# power.net
KiCad netlist of a schematic drawn in Altium Designer
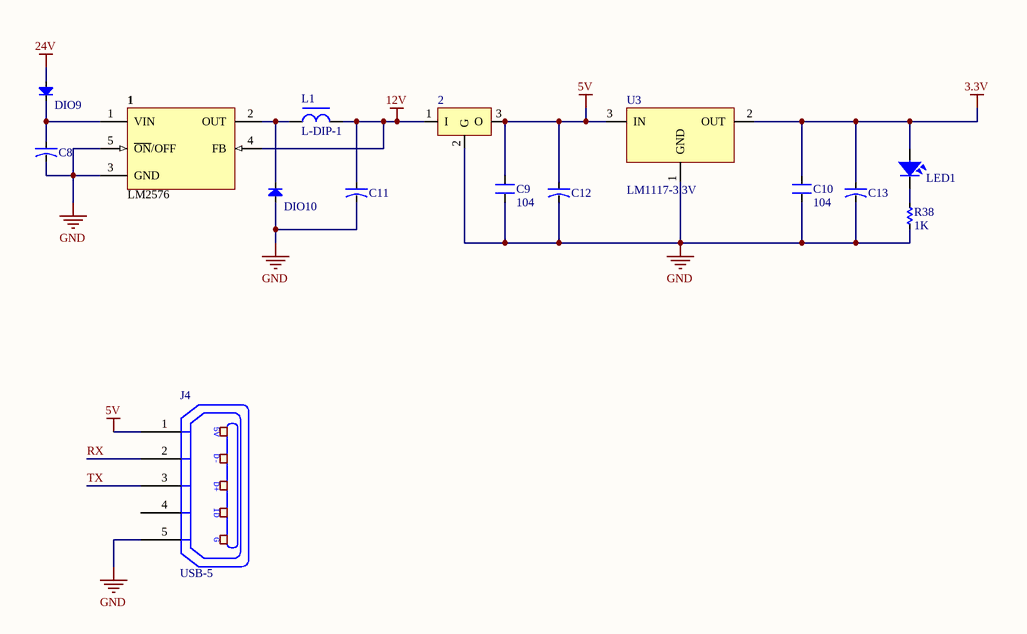
[diagram p0: power.SchDoc]

(export (version "E")
  (design (tool "Eeschema 10.0.6"))
  (components
    (comp (ref "1") (value "LM2576") (footprint "TO263") (libsource (lib "LIBRARY") (part "LM2576")))
    (comp (ref "2")
      (value "LM78xx")
      (footprint "TO252-123")
      (description "Positive Voltage Regulator")
      (fields (field (name "PUBLISHER") "Altium Limited"))
      (libsource (lib "LIBRARY") (part "LM78xx"))
    )
    (comp (ref "C8")
      (value "CN-ALU-SMD")
      (footprint "CAP-ALU-SMD-4.5x5x1.4")
      (description "Polarized Capacitor (Axial)")
      (fields (field (name "PUBLISHER") "Altium Limited"))
      (libsource (lib "LIBTanCN") (part "CN-ALU-SMD"))
    )
    (comp (ref "C9")
      (value "104")
      (footprint "SM-CAP-0805")
      (fields (field (name "DESIGNED BY") "VanDungEvn"))
      (libsource (lib "electronicvn-library1") (part "CN"))
    )
    (comp (ref "C10")
      (value "104")
      (footprint "SM-CAP-0805")
      (fields (field (name "DESIGNED BY") "VanDungEvn"))
      (libsource (lib "electronicvn-library1") (part "CN"))
    )
    (comp (ref "C11")
      (value "CN-ALU-SMD")
      (footprint "CAP-ALU-SMD-4.5x5x1.4")
      (description "Polarized Capacitor (Axial)")
      (fields (field (name "PUBLISHER") "Altium Limited"))
      (libsource (lib "LIBTanCN") (part "CN-ALU-SMD"))
    )
    (comp (ref "C12")
      (value "CN-ALU-SMD")
      (footprint "CAP-ALU-SMD-4.5x5x1.4")
      (description "Polarized Capacitor (Axial)")
      (fields (field (name "PUBLISHER") "Altium Limited"))
      (libsource (lib "LIBTanCN") (part "CN-ALU-SMD"))
    )
    (comp (ref "C13")
      (value "CN-ALU-SMD")
      (footprint "CAP-ALU-SMD-4.5x5x1.4")
      (description "Polarized Capacitor (Axial)")
      (fields (field (name "PUBLISHER") "Altium Limited"))
      (libsource (lib "LIBTanCN") (part "CN-ALU-SMD"))
    )
    (comp (ref "DIO9")
      (value "Diode SMD")
      (footprint "DIO-SMD-106")
      (description "Default Diode")
      (fields (field (name "PUBLISHER") "Altium Limited"))
      (libsource (lib "LIBRARY") (part "Diode SMD"))
    )
    (comp (ref "DIO10")
      (value "Diode SMD")
      (footprint "DIO-SMD-106")
      (description "Default Diode")
      (fields (field (name "PUBLISHER") "Altium Limited"))
      (libsource (lib "LIBRARY") (part "Diode SMD"))
    )
    (comp (ref "J4")
      (value "USB-5")
      (footprint "USB-M4")
      (fields
        (field (name "MANUFACTURER") "FCI")
        (field (name "MANUFACTURER PART NUMBER") "10118193-0001LF")
        (field (name ".CREATOR") "MM")
        (field (name ".CHECKED PCB") "RF")
        (field (name ".CHECKED SCH") "MM")
      )
      (libsource (lib "LIBRARY") (part "USB-5"))
    )
    (comp (ref "L1")
      (value "L-DIP-1")
      (footprint "L-DIP-M-13.5x6")
      (description "Inductor")
      (libsource (lib "LIBRARY") (part "L-DIP-1"))
    )
    (comp (ref "LED1") (value "LED") (footprint "LED-0805-Blue") (libsource (lib "LIBRARY") (part "LED SMD")))
    (comp (ref "R38")
      (value "1K")
      (footprint "RES-SMD-0805")
      (description "Resistor")
      (fields
        (field (name "MANUFACTURER") "Generic Components")
        (field (name "PUBLISHER") "Altium Hobart Technology Centre")
      )
      (libsource (lib "LIBRARY") (part "Res-SMD"))
    )
    (comp (ref "U3")
      (value "LM1117-3.3V")
      (footprint "SOT223")
      (description "800mA Low-Dropout Linear Regulator")
      (fields (field (name "CREATOR") "Nguyen Ba Bien"))
      (libsource (lib "LIBRARY") (part "LM1117"))
    )
  )
  (nets
    (net (code "1") (name "/RX") (class "Default")
      (node (ref "J4") (pin "2") (pinfunction "P2_2") (pintype "passive"))
    )
    (net (code "2") (name "/TX") (class "Default")
      (node (ref "J4") (pin "3") (pinfunction "P3_3") (pintype "passive"))
    )
    (net (code "3") (name "3.3V") (class "Default")
      (node (ref "C10") (pin "2") (pinfunction "2_2") (pintype "passive"))
      (node (ref "C13") (pin "1") (pinfunction "1_1") (pintype "passive"))
      (node (ref "LED1") (pin "1") (pinfunction "1_1") (pintype "passive"))
      (node (ref "U3") (pin "2") (pinfunction "OUT_2") (pintype "passive"))
    )
    (net (code "4") (name "5V") (class "Default")
      (node (ref "2") (pin "3") (pinfunction "O_3") (pintype "power_in"))
      (node (ref "C12") (pin "1") (pinfunction "1_1") (pintype "passive"))
      (node (ref "C9") (pin "2") (pinfunction "2_2") (pintype "passive"))
      (node (ref "J4") (pin "1") (pinfunction "P1_1") (pintype "passive"))
      (node (ref "U3") (pin "3") (pinfunction "IN_3") (pintype "passive"))
    )
    (net (code "5") (name "12V") (class "Default")
      (node (ref "1") (pin "4") (pinfunction "FB_4") (pintype "input"))
      (node (ref "2") (pin "1") (pinfunction "I_1") (pintype "power_in"))
      (node (ref "C11") (pin "1") (pinfunction "1_1") (pintype "passive"))
      (node (ref "L1") (pin "2") (pinfunction "2_2") (pintype "passive"))
    )
    (net (code "6") (name "24V") (class "Default")
      (node (ref "DIO9") (pin "1") (pinfunction "A_1") (pintype "passive"))
    )
    (net (code "7") (name "GND") (class "Default")
      (node (ref "1") (pin "3") (pinfunction "GND_3") (pintype "power_in"))
      (node (ref "1") (pin "5") (pinfunction "~{ON}/OFF_5") (pintype "input"))
      (node (ref "2") (pin "2") (pinfunction "G_2") (pintype "power_in"))
      (node (ref "C10") (pin "1") (pinfunction "1_1") (pintype "passive"))
      (node (ref "C11") (pin "2") (pinfunction "2_2") (pintype "passive"))
      (node (ref "C12") (pin "2") (pinfunction "2_2") (pintype "passive"))
      (node (ref "C13") (pin "2") (pinfunction "2_2") (pintype "passive"))
      (node (ref "C8") (pin "2") (pinfunction "2_2") (pintype "passive"))
      (node (ref "C9") (pin "1") (pinfunction "1_1") (pintype "passive"))
      (node (ref "DIO10") (pin "1") (pinfunction "A_1") (pintype "passive"))
      (node (ref "J4") (pin "5") (pinfunction "P5_5") (pintype "passive"))
      (node (ref "R38") (pin "1") (pinfunction "1_1") (pintype "passive"))
      (node (ref "U3") (pin "1") (pinfunction "GND_1") (pintype "passive"))
    )
    (net (code "8") (name "Net-(1-OUT)") (class "Default")
      (node (ref "1") (pin "2") (pinfunction "OUT_2") (pintype "power_in"))
      (node (ref "DIO10") (pin "2") (pinfunction "K_2") (pintype "passive"))
      (node (ref "L1") (pin "1") (pinfunction "1_1") (pintype "passive"))
    )
    (net (code "9") (name "Net-(1-VIN)") (class "Default")
      (node (ref "1") (pin "1") (pinfunction "VIN_1") (pintype "power_in"))
      (node (ref "C8") (pin "1") (pinfunction "1_1") (pintype "passive"))
      (node (ref "DIO9") (pin "2") (pinfunction "K_2") (pintype "passive"))
    )
    (net (code "10") (name "Net-(LED1-Pad2)") (class "Default")
      (node (ref "LED1") (pin "2") (pinfunction "2_2") (pintype "passive"))
      (node (ref "R38") (pin "2") (pinfunction "2_2") (pintype "passive"))
    )
    (net (code "11") (name "unconnected-(J4-P4-Pad4)") (class "Default")
      (node (ref "J4") (pin "4") (pinfunction "P4_4") (pintype "passive"))
    )
  )
)
